# rs_connection.net
KiCad netlist of a schematic drawn in Altium Designer
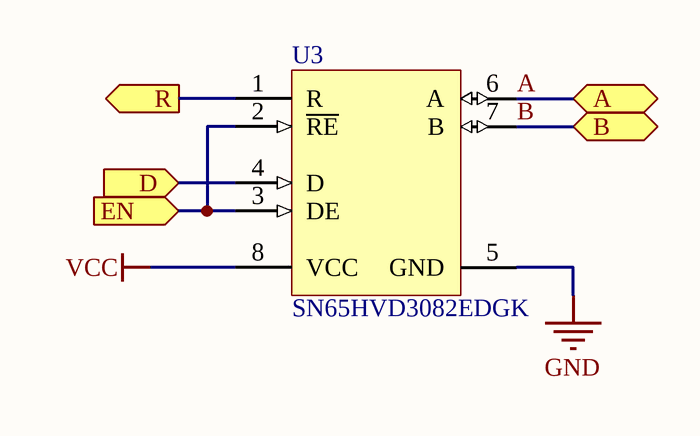
[diagram p0: rs_connection.SchDoc]

(export (version "E")
  (design (tool "Eeschema 10.0.6"))
  (components
    (comp (ref "U3")
      (value "SN65HVD3082EDGK")
      (footprint "DGK8_L")
      (fields (field (name "MANUFACTURER") "Texas Instruments"))
      (libsource (lib "Texas Instruments Interface RS-485") (part "SN65HVD3082EDGK"))
    )
  )
  (nets
    (net (code "1") (name "/A") (class "Default")
      (node (ref "U3") (pin "6") (pinfunction "A_6") (pintype "bidirectional"))
    )
    (net (code "2") (name "/B") (class "Default")
      (node (ref "U3") (pin "7") (pinfunction "B_7") (pintype "bidirectional"))
    )
    (net (code "3") (name "/D") (class "Default")
      (node (ref "U3") (pin "4") (pinfunction "D_4") (pintype "input"))
    )
    (net (code "4") (name "/EN") (class "Default")
      (node (ref "U3") (pin "2") (pinfunction "~{RE}_2") (pintype "input"))
      (node (ref "U3") (pin "3") (pinfunction "DE_3") (pintype "input"))
    )
    (net (code "5") (name "/R") (class "Default")
      (node (ref "U3") (pin "1") (pinfunction "R_1") (pintype "tri_state"))
    )
    (net (code "6") (name "GND") (class "Default")
      (node (ref "U3") (pin "5") (pinfunction "GND_5") (pintype "power_in"))
    )
    (net (code "7") (name "VCC") (class "Default")
      (node (ref "U3") (pin "8") (pinfunction "VCC_8") (pintype "power_in"))
    )
  )
)
